# IRRX.net
KiCad netlist of a schematic drawn in EAGLE
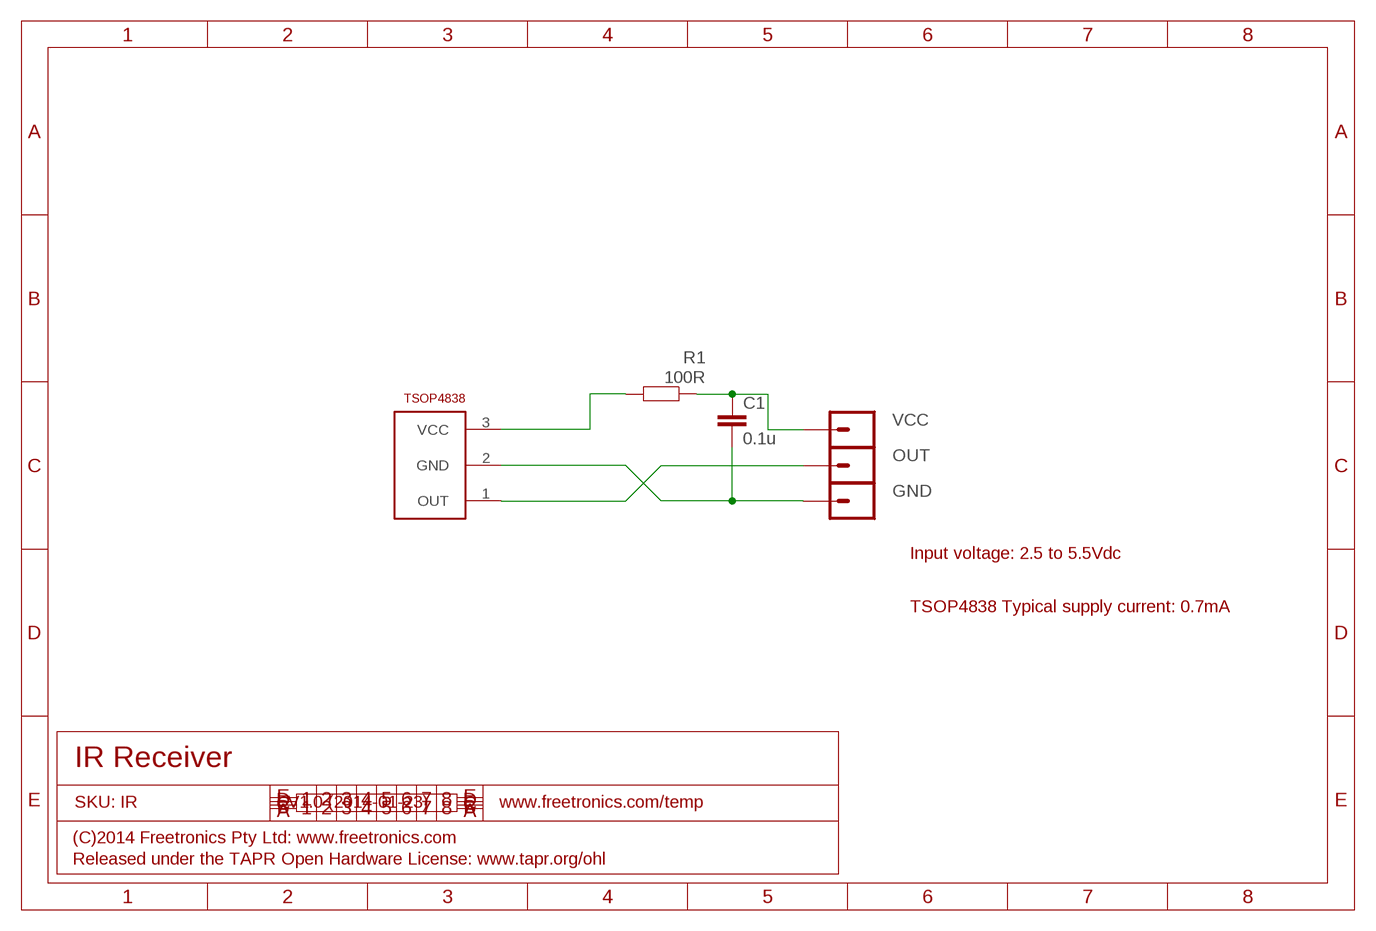
[diagram p0: schematic, sheet 1]

(export (version "E")
  (design (tool "Eeschema 10.0.6"))
  (components
    (comp (ref "C1")
      (value "0.1u")
      (footprint "eagle-import:0603")
      (libsource (lib "eagle-import") (part "CAP0603"))
    )
    (comp (ref "GND")
      (value "M01PTH")
      (footprint "eagle-import:1X01")
      (libsource (lib "eagle-import") (part "M01PTH"))
    )
    (comp (ref "OUT")
      (value "M01PTH")
      (footprint "eagle-import:1X01")
      (libsource (lib "eagle-import") (part "M01PTH"))
    )
    (comp (ref "R1")
      (value "100R")
      (footprint "eagle-import:0603")
      (libsource (lib "eagle-import") (part "RESISTOR0603"))
    )
    (comp (ref "TSOP4838")
      (value "TSOP4838")
      (footprint "eagle-import:TO220")
      (libsource (lib "eagle-import") (part "TSOP4838"))
    )
    (comp (ref "VCC")
      (value "M01PTH")
      (footprint "eagle-import:1X01")
      (libsource (lib "eagle-import") (part "M01PTH"))
    )
  )
  (nets
    (net (code "1") (name "Net-(C1-Pad1)") (class "Default")
      (node (ref "C1") (pin "1") (pinfunction "1_1") (pintype "passive"))
      (node (ref "R1") (pin "1") (pinfunction "1_1") (pintype "passive"))
      (node (ref "VCC") (pin "1") (pinfunction "1_1") (pintype "passive"))
    )
    (net (code "2") (name "Net-(TSOP4838-GND)") (class "Default")
      (node (ref "C1") (pin "2") (pinfunction "2_2") (pintype "passive"))
      (node (ref "GND") (pin "1") (pinfunction "1_1") (pintype "passive"))
      (node (ref "TSOP4838") (pin "2") (pinfunction "GND_2") (pintype "bidirectional"))
    )
    (net (code "3") (name "Net-(TSOP4838-OUT)") (class "Default")
      (node (ref "OUT") (pin "1") (pinfunction "1_1") (pintype "passive"))
      (node (ref "TSOP4838") (pin "1") (pinfunction "OUT_1") (pintype "bidirectional"))
    )
    (net (code "4") (name "Net-(TSOP4838-VCC)") (class "Default")
      (node (ref "R1") (pin "2") (pinfunction "2_2") (pintype "passive"))
      (node (ref "TSOP4838") (pin "3") (pinfunction "VCC_3") (pintype "bidirectional"))
    )
  )
)
